# EnviromentalElements.net
KiCad netlist of a schematic drawn in Altium Designer
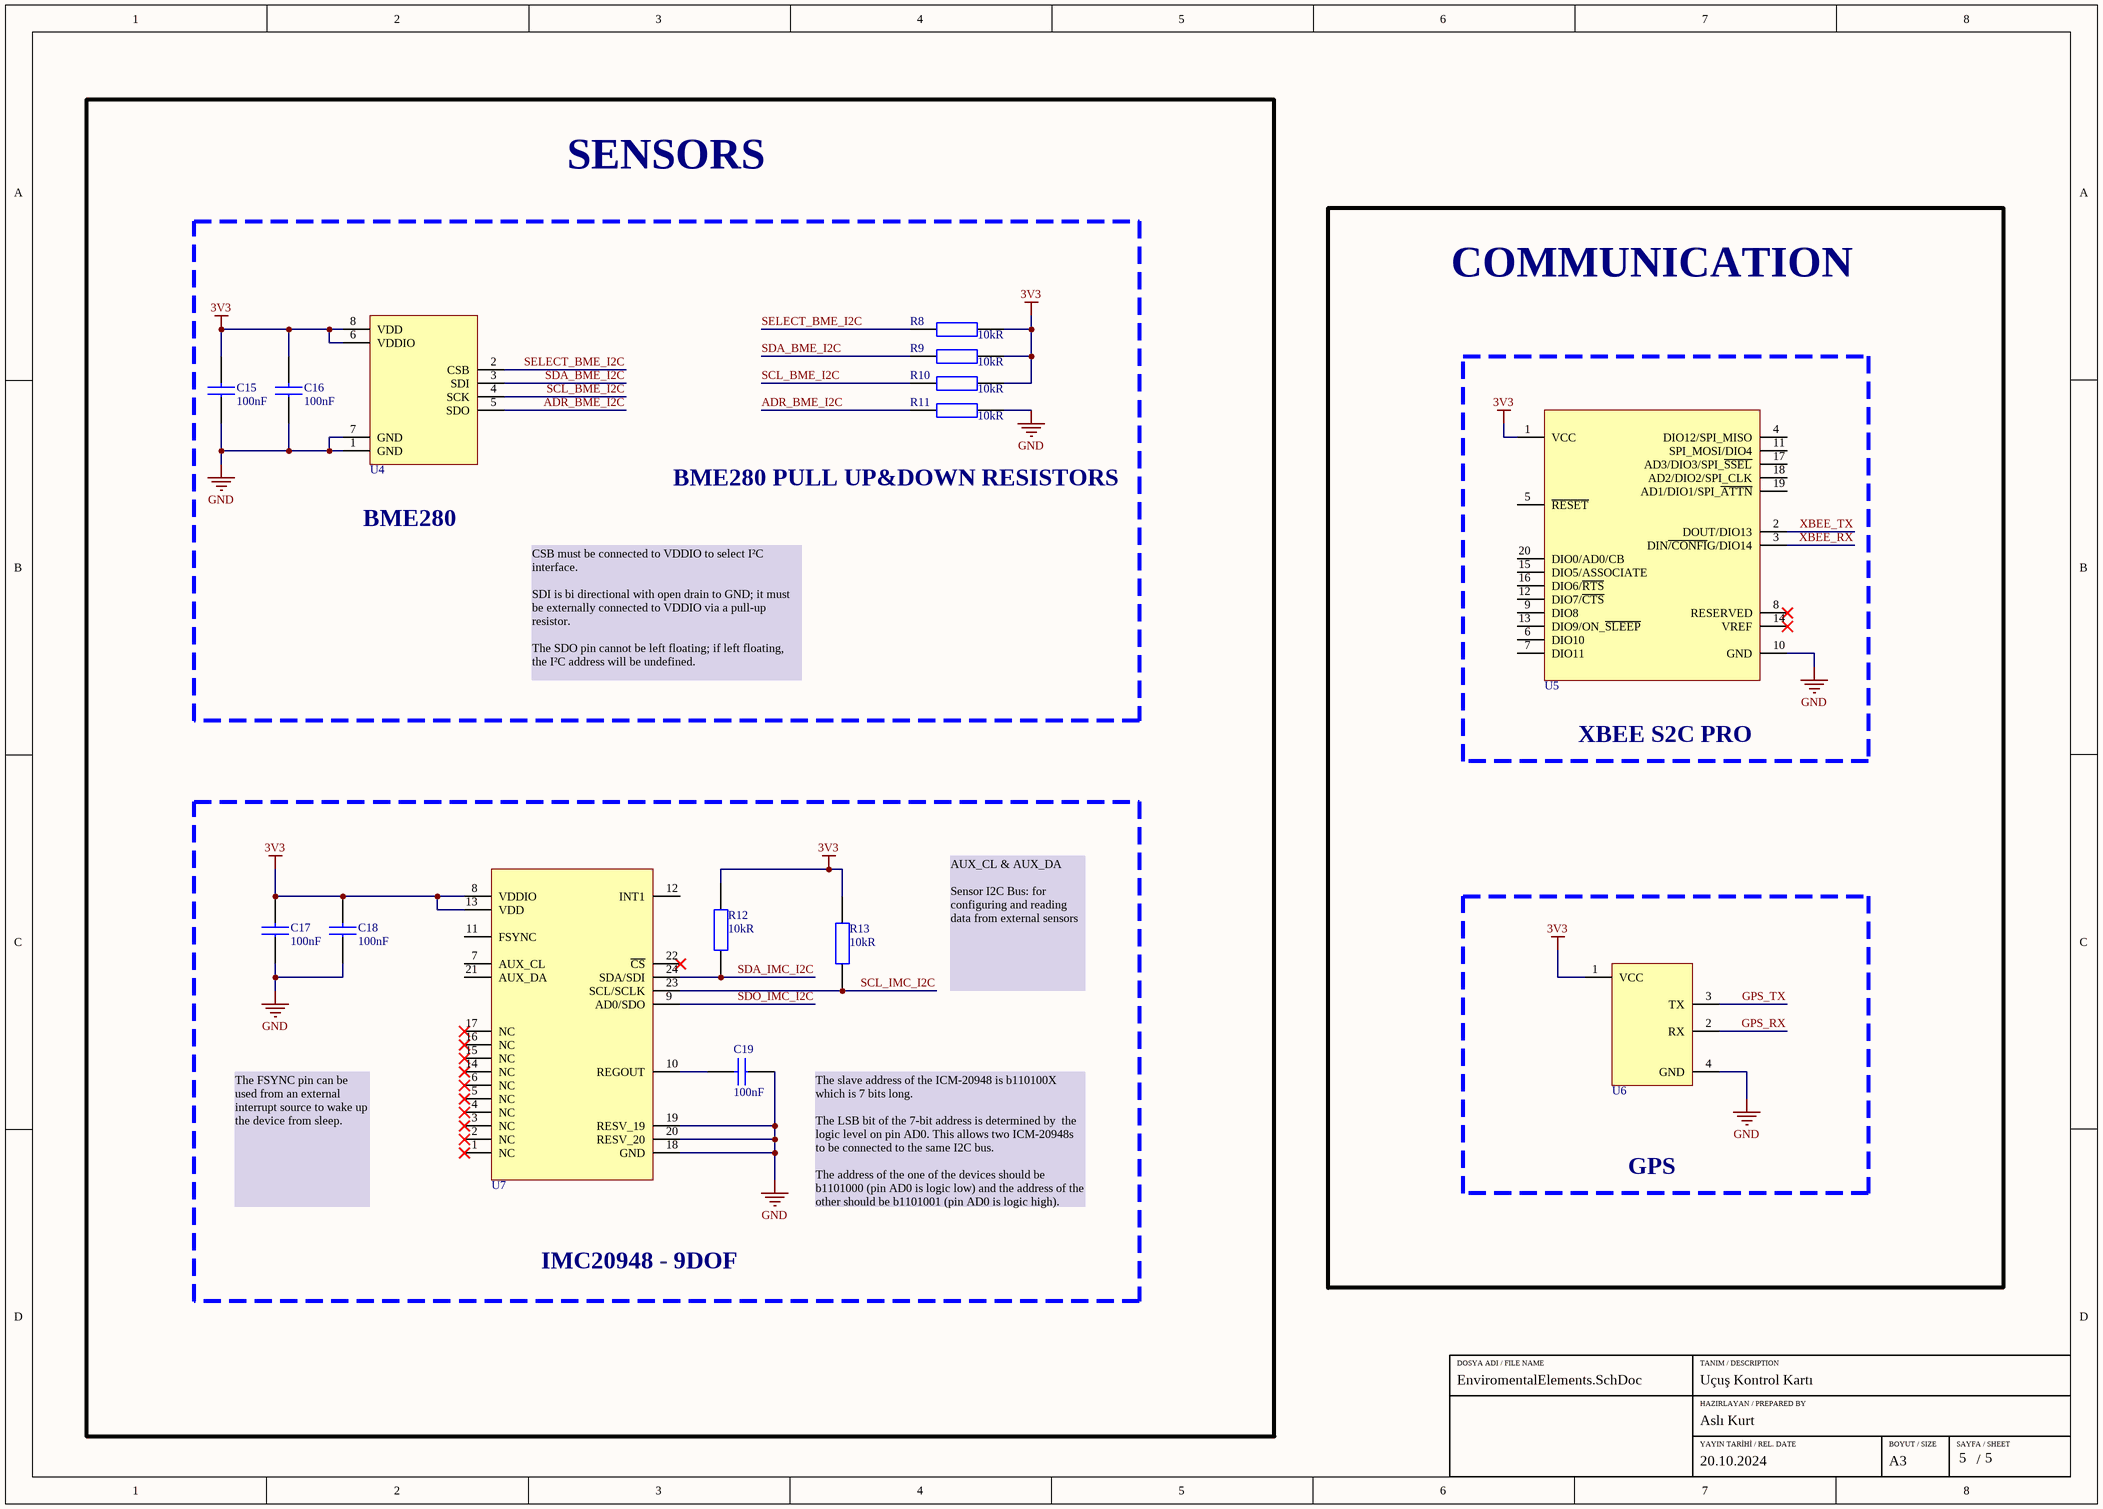
[diagram p0: EnviromentalElements.SchDoc]

(export (version "E")
  (design (tool "Eeschema 10.0.6"))
  (components
    (comp (ref "C15")
      (value "C0603C104K5RACTU")
      (footprint "CAP_0603")
      (description "CAP CER 100nF %10 0603 SMD")
      (fields
        (field (name "MANUFACTURER") "KEMET")
        (field (name "TOLERANCE") "10%")
        (field (name "CAPACITANCE") "100nF")
        (field (name "DESIGNEDBY") "Aslı Kurt")
      )
      (libsource (lib "MyLibrary") (part "CAP CER 100nF 0603"))
    )
    (comp (ref "C16")
      (value "C0603C104K5RACTU")
      (footprint "CAP_0603")
      (description "CAP CER 100nF %10 0603 SMD")
      (fields
        (field (name "MANUFACTURER") "KEMET")
        (field (name "TOLERANCE") "10%")
        (field (name "CAPACITANCE") "100nF")
        (field (name "DESIGNEDBY") "Aslı Kurt")
      )
      (libsource (lib "MyLibrary") (part "CAP CER 100nF 0603"))
    )
    (comp (ref "C17")
      (value "C0603C104K5RACTU")
      (footprint "CAP_0603")
      (description "CAP CER 100nF %10 0603 SMD")
      (fields
        (field (name "MANUFACTURER") "KEMET")
        (field (name "TOLERANCE") "10%")
        (field (name "CAPACITANCE") "100nF")
        (field (name "DESIGNEDBY") "Aslı Kurt")
      )
      (libsource (lib "MyLibrary") (part "CAP CER 100nF 0603"))
    )
    (comp (ref "C18")
      (value "C0603C104K5RACTU")
      (footprint "CAP_0603")
      (description "CAP CER 100nF %10 0603 SMD")
      (fields
        (field (name "MANUFACTURER") "KEMET")
        (field (name "TOLERANCE") "10%")
        (field (name "CAPACITANCE") "100nF")
        (field (name "DESIGNEDBY") "Aslı Kurt")
      )
      (libsource (lib "MyLibrary") (part "CAP CER 100nF 0603"))
    )
    (comp (ref "C19")
      (value "C0603C104K5RACTU")
      (footprint "CAP_0603")
      (description "CAP CER 100nF %10 0603 SMD")
      (fields
        (field (name "MANUFACTURER") "KEMET")
        (field (name "TOLERANCE") "10%")
        (field (name "CAPACITANCE") "100nF")
        (field (name "DESIGNEDBY") "Aslı Kurt")
      )
      (libsource (lib "MyLibrary") (part "CAP CER 100nF 0603"))
    )
    (comp (ref "R8")
      (value "RC0603FR-0710KL")
      (footprint "RES_0603")
      (description "RES 10K %1 OHM 0603 SMD")
      (fields
        (field (name "MANUFACTURER") "Yageo")
        (field (name "TOLERANCE") "1%")
        (field (name "RESISTANCE") "10kR")
        (field (name "DESIGNEDBY") "Aslı Kurt")
      )
      (libsource (lib "MyLibrary") (part "RES 10K OHM 0603"))
    )
    (comp (ref "R9")
      (value "RC0603FR-0710KL")
      (footprint "RES_0603")
      (description "RES 10K %1 OHM 0603 SMD")
      (fields
        (field (name "MANUFACTURER") "Yageo")
        (field (name "TOLERANCE") "1%")
        (field (name "RESISTANCE") "10kR")
        (field (name "DESIGNEDBY") "Aslı Kurt")
      )
      (libsource (lib "MyLibrary") (part "RES 10K OHM 0603"))
    )
    (comp (ref "R10")
      (value "RC0603FR-0710KL")
      (footprint "RES_0603")
      (description "RES 10K %1 OHM 0603 SMD")
      (fields
        (field (name "MANUFACTURER") "Yageo")
        (field (name "TOLERANCE") "1%")
        (field (name "RESISTANCE") "10kR")
        (field (name "DESIGNEDBY") "Aslı Kurt")
      )
      (libsource (lib "MyLibrary") (part "RES 10K OHM 0603"))
    )
    (comp (ref "R11")
      (value "RC0603FR-0710KL")
      (footprint "RES_0603")
      (description "RES 10K %1 OHM 0603 SMD")
      (fields
        (field (name "MANUFACTURER") "Yageo")
        (field (name "TOLERANCE") "1%")
        (field (name "RESISTANCE") "10kR")
        (field (name "DESIGNEDBY") "Aslı Kurt")
      )
      (libsource (lib "MyLibrary") (part "RES 10K OHM 0603"))
    )
    (comp (ref "R12")
      (value "RC0603FR-0710KL")
      (footprint "RES_0603")
      (description "RES 10K %1 OHM 0603 SMD")
      (fields
        (field (name "MANUFACTURER") "Yageo")
        (field (name "TOLERANCE") "1%")
        (field (name "RESISTANCE") "10kR")
        (field (name "DESIGNEDBY") "Aslı Kurt")
      )
      (libsource (lib "") (part "RES 10K OHM 0603_1"))
    )
    (comp (ref "R13")
      (value "RC0603FR-0710KL")
      (footprint "RES_0603")
      (description "RES 10K %1 OHM 0603 SMD")
      (fields
        (field (name "MANUFACTURER") "Yageo")
        (field (name "TOLERANCE") "1%")
        (field (name "RESISTANCE") "10kR")
        (field (name "DESIGNEDBY") "Aslı Kurt")
      )
      (libsource (lib "") (part "RES 10K OHM 0603_1"))
    )
    (comp (ref "U4")
      (value "BME280")
      (footprint "8-VFLGA")
      (description "Pressure, Temperature and Humidity Sensor Digital Output 1.8V 8-Pin LGA T/R")
      (fields (field (name "MANUFACTURER") "Bosch") (field (name "DESIGNEDBY") "Aslı Kurt"))
      (libsource (lib "MyLibrary") (part "BME280"))
    )
    (comp (ref "U5")
      (value "XBEE S2C PRO")
      (footprint "XBEE_S2C_PRO")
      (description "XBee S2C 802.15.4, 2.4GHz TH (RPSMA)")
      (fields
        (field (name "MANUFACTURER") "Digi International")
        (field (name "MANUFACTURER PART NUMBER") "XB24CASIT-001")
        (field (name "DESIGNEDBY") "Aslı Kurt")
      )
      (libsource (lib "MyLibrary") (part "XB24CASIT-001"))
    )
    (comp (ref "U6")
      (value "GY-NEO6MV2")
      (footprint "GY-NEO6MV2")
      (description "GY-NEO6MV2 GPS Modülü - Uçuş Kontrol Sistem GPS'i")
      (fields (field (name "DESIGNEDBY") "Aslı Kurt"))
      (libsource (lib "MyLibrary") (part "GY-NEO6MV2"))
    )
    (comp (ref "U7")
      (value "ICM-20948")
      (footprint "24-TFQFN Module Exposed Pad")
      (description "Accelerometer and Gyroscope Compass 9-Axis Digital 24-Pin QFN T/R")
      (fields (field (name "MANUFACTURER") "TDK") (field (name "DESIGNEDBY") "Aslı Kurt"))
      (libsource (lib "MyLibrary") (part "ICM-20948"))
    )
  )
  (nets
    (net (code "1") (name "/ADR_BME_I2C") (class "Default")
      (node (ref "R11") (pin "1") (pinfunction "1_1") (pintype "passive"))
      (node (ref "U4") (pin "5") (pinfunction "SDO_5") (pintype "passive"))
    )
    (net (code "2") (name "/GPS_RX") (class "Default")
      (node (ref "U6") (pin "2") (pinfunction "RX_2") (pintype "passive"))
    )
    (net (code "3") (name "/GPS_TX") (class "Default")
      (node (ref "U6") (pin "3") (pinfunction "TX_3") (pintype "passive"))
    )
    (net (code "4") (name "/SCL_BME_I2C") (class "Default")
      (node (ref "R10") (pin "1") (pinfunction "1_1") (pintype "passive"))
      (node (ref "U4") (pin "4") (pinfunction "SCK_4") (pintype "passive"))
    )
    (net (code "5") (name "/SCL_IMC_I2C") (class "Default")
      (node (ref "R13") (pin "1") (pinfunction "1_1") (pintype "passive"))
      (node (ref "U7") (pin "23") (pinfunction "SCL/SCLK_23") (pintype "passive"))
    )
    (net (code "6") (name "/SDA_BME_I2C") (class "Default")
      (node (ref "R9") (pin "1") (pinfunction "1_1") (pintype "passive"))
      (node (ref "U4") (pin "3") (pinfunction "SDI_3") (pintype "passive"))
    )
    (net (code "7") (name "/SDA_IMC_I2C") (class "Default")
      (node (ref "R12") (pin "1") (pinfunction "1_1") (pintype "passive"))
      (node (ref "U7") (pin "24") (pinfunction "SDA/SDI_24") (pintype "passive"))
    )
    (net (code "8") (name "/SDO_IMC_I2C") (class "Default")
      (node (ref "U7") (pin "9") (pinfunction "AD0/SDO_9") (pintype "passive"))
    )
    (net (code "9") (name "/SELECT_BME_I2C") (class "Default")
      (node (ref "R8") (pin "1") (pinfunction "1_1") (pintype "passive"))
      (node (ref "U4") (pin "2") (pinfunction "CSB_2") (pintype "passive"))
    )
    (net (code "10") (name "/XBEE_RX") (class "Default")
      (node (ref "U5") (pin "3") (pinfunction "DIN~{/CONFI}G/DIO14_3") (pintype "passive"))
    )
    (net (code "11") (name "/XBEE_TX") (class "Default")
      (node (ref "U5") (pin "2") (pinfunction "DOUT/DIO13_2") (pintype "passive"))
    )
    (net (code "12") (name "3V3") (class "Default")
      (node (ref "C15") (pin "2") (pinfunction "2_2") (pintype "passive"))
      (node (ref "C16") (pin "2") (pinfunction "2_2") (pintype "passive"))
      (node (ref "C17") (pin "2") (pinfunction "2_2") (pintype "passive"))
      (node (ref "C18") (pin "2") (pinfunction "2_2") (pintype "passive"))
      (node (ref "R10") (pin "2") (pinfunction "2_2") (pintype "passive"))
      (node (ref "R12") (pin "2") (pinfunction "2_2") (pintype "passive"))
      (node (ref "R13") (pin "2") (pinfunction "2_2") (pintype "passive"))
      (node (ref "R8") (pin "2") (pinfunction "2_2") (pintype "passive"))
      (node (ref "R9") (pin "2") (pinfunction "2_2") (pintype "passive"))
      (node (ref "U4") (pin "6") (pinfunction "VDDIO_6") (pintype "passive"))
      (node (ref "U4") (pin "8") (pinfunction "VDD_8") (pintype "passive"))
      (node (ref "U5") (pin "1") (pinfunction "VCC_1") (pintype "passive"))
      (node (ref "U6") (pin "1") (pinfunction "VCC_1") (pintype "passive"))
      (node (ref "U7") (pin "13") (pinfunction "VDD_13") (pintype "passive"))
      (node (ref "U7") (pin "8") (pinfunction "VDDIO_8") (pintype "passive"))
    )
    (net (code "13") (name "GND") (class "Default")
      (node (ref "C15") (pin "1") (pinfunction "1_1") (pintype "passive"))
      (node (ref "C16") (pin "1") (pinfunction "1_1") (pintype "passive"))
      (node (ref "C17") (pin "1") (pinfunction "1_1") (pintype "passive"))
      (node (ref "C18") (pin "1") (pinfunction "1_1") (pintype "passive"))
      (node (ref "C19") (pin "1") (pinfunction "1_1") (pintype "passive"))
      (node (ref "R11") (pin "2") (pinfunction "2_2") (pintype "passive"))
      (node (ref "U4") (pin "1") (pinfunction "GND_1") (pintype "passive"))
      (node (ref "U4") (pin "7") (pinfunction "GND_7") (pintype "passive"))
      (node (ref "U5") (pin "10") (pinfunction "GND_10") (pintype "passive"))
      (node (ref "U6") (pin "4") (pinfunction "GND_4") (pintype "passive"))
      (node (ref "U7") (pin "18") (pinfunction "GND_18") (pintype "passive"))
      (node (ref "U7") (pin "19") (pinfunction "RESV_19_19") (pintype "passive"))
      (node (ref "U7") (pin "20") (pinfunction "RESV_20_20") (pintype "passive"))
    )
    (net (code "14") (name "Net-(U7-REGOUT)") (class "Default")
      (node (ref "C19") (pin "2") (pinfunction "2_2") (pintype "passive"))
      (node (ref "U7") (pin "10") (pinfunction "REGOUT_10") (pintype "passive"))
    )
    (net (code "15") (name "unconnected-(U5-AD1{slash}DIO1{slash}SPI_~{ATTN}-Pad19)") (class "Default")
      (node (ref "U5") (pin "19") (pinfunction "AD1/DIO1/SPI_~{ATTN}_19") (pintype "passive"))
    )
    (net (code "16") (name "unconnected-(U5-AD2{slash}DIO2{slash}SPI_CLK-Pad18)") (class "Default")
      (node (ref "U5") (pin "18") (pinfunction "AD2/DIO2/SPI_CLK_18") (pintype "passive"))
    )
    (net (code "17") (name "unconnected-(U5-AD3{slash}DIO3{slash}SPI_~{SSEL}-Pad17)") (class "Default")
      (node (ref "U5") (pin "17") (pinfunction "AD3/DIO3/SPI_~{SSEL}_17") (pintype "passive"))
    )
    (net (code "18") (name "unconnected-(U5-DIO0{slash}AD0{slash}CB-Pad20)") (class "Default")
      (node (ref "U5") (pin "20") (pinfunction "DIO0/AD0/CB_20") (pintype "passive"))
    )
    (net (code "19") (name "unconnected-(U5-DIO5{slash}ASSOCIATE-Pad15)") (class "Default")
      (node (ref "U5") (pin "15") (pinfunction "DIO5/ASSOCIATE_15") (pintype "passive"))
    )
    (net (code "20") (name "unconnected-(U5-DIO6{slash}~{RTS}-Pad16)") (class "Default")
      (node (ref "U5") (pin "16") (pinfunction "DIO6/~{RTS}_16") (pintype "passive"))
    )
    (net (code "21") (name "unconnected-(U5-DIO7{slash}~{CTS}-Pad12)") (class "Default")
      (node (ref "U5") (pin "12") (pinfunction "DIO7/~{CTS}_12") (pintype "passive"))
    )
    (net (code "22") (name "unconnected-(U5-DIO8-Pad9)") (class "Default")
      (node (ref "U5") (pin "9") (pinfunction "DIO8_9") (pintype "passive"))
    )
    (net (code "23") (name "unconnected-(U5-DIO9{slash}ON_~{SLEEP}-Pad13)") (class "Default")
      (node (ref "U5") (pin "13") (pinfunction "DIO9/ON_~{SLEEP}_13") (pintype "passive"))
    )
    (net (code "24") (name "unconnected-(U5-DIO10-Pad6)") (class "Default")
      (node (ref "U5") (pin "6") (pinfunction "DIO10_6") (pintype "passive"))
    )
    (net (code "25") (name "unconnected-(U5-DIO11-Pad7)") (class "Default")
      (node (ref "U5") (pin "7") (pinfunction "DIO11_7") (pintype "passive"))
    )
    (net (code "26") (name "unconnected-(U5-DIO12{slash}SPI_MISO-Pad4)") (class "Default")
      (node (ref "U5") (pin "4") (pinfunction "DIO12/SPI_MISO_4") (pintype "passive"))
    )
    (net (code "27") (name "unconnected-(U5-RESERVED-Pad8)") (class "Default")
      (node (ref "U5") (pin "8") (pinfunction "RESERVED_8") (pintype "passive+no_connect"))
    )
    (net (code "28") (name "unconnected-(U5-SPI_MOSI{slash}DIO4-Pad11)") (class "Default")
      (node (ref "U5") (pin "11") (pinfunction "SPI_MOSI/DIO4_11") (pintype "passive"))
    )
    (net (code "29") (name "unconnected-(U5-VREF-Pad14)") (class "Default")
      (node (ref "U5") (pin "14") (pinfunction "VREF_14") (pintype "passive+no_connect"))
    )
    (net (code "30") (name "unconnected-(U5-~{RESET}-Pad5)") (class "Default")
      (node (ref "U5") (pin "5") (pinfunction "~{RESET}_5") (pintype "passive"))
    )
    (net (code "31") (name "unconnected-(U7-AUX_CL-Pad7)") (class "Default")
      (node (ref "U7") (pin "7") (pinfunction "AUX_CL_7") (pintype "passive"))
    )
    (net (code "32") (name "unconnected-(U7-AUX_DA-Pad21)") (class "Default")
      (node (ref "U7") (pin "21") (pinfunction "AUX_DA_21") (pintype "passive"))
    )
    (net (code "33") (name "unconnected-(U7-FSYNC-Pad11)") (class "Default")
      (node (ref "U7") (pin "11") (pinfunction "FSYNC_11") (pintype "passive"))
    )
    (net (code "34") (name "unconnected-(U7-INT1-Pad12)") (class "Default")
      (node (ref "U7") (pin "12") (pinfunction "INT1_12") (pintype "passive"))
    )
    (net (code "35") (name "unconnected-(U7-NC-Pad1)") (class "Default")
      (node (ref "U7") (pin "1") (pinfunction "NC_1") (pintype "passive+no_connect"))
    )
    (net (code "36") (name "unconnected-(U7-NC-Pad2)") (class "Default")
      (node (ref "U7") (pin "2") (pinfunction "NC_2") (pintype "passive+no_connect"))
    )
    (net (code "37") (name "unconnected-(U7-NC-Pad3)") (class "Default")
      (node (ref "U7") (pin "3") (pinfunction "NC_3") (pintype "passive+no_connect"))
    )
    (net (code "38") (name "unconnected-(U7-NC-Pad4)") (class "Default")
      (node (ref "U7") (pin "4") (pinfunction "NC_4") (pintype "passive+no_connect"))
    )
    (net (code "39") (name "unconnected-(U7-NC-Pad5)") (class "Default")
      (node (ref "U7") (pin "5") (pinfunction "NC_5") (pintype "passive+no_connect"))
    )
    (net (code "40") (name "unconnected-(U7-NC-Pad6)") (class "Default")
      (node (ref "U7") (pin "6") (pinfunction "NC_6") (pintype "passive+no_connect"))
    )
    (net (code "41") (name "unconnected-(U7-NC-Pad14)") (class "Default")
      (node (ref "U7") (pin "14") (pinfunction "NC_14") (pintype "passive+no_connect"))
    )
    (net (code "42") (name "unconnected-(U7-NC-Pad15)") (class "Default")
      (node (ref "U7") (pin "15") (pinfunction "NC_15") (pintype "passive+no_connect"))
    )
    (net (code "43") (name "unconnected-(U7-NC-Pad16)") (class "Default")
      (node (ref "U7") (pin "16") (pinfunction "NC_16") (pintype "passive+no_connect"))
    )
    (net (code "44") (name "unconnected-(U7-NC-Pad17)") (class "Default")
      (node (ref "U7") (pin "17") (pinfunction "NC_17") (pintype "passive+no_connect"))
    )
    (net (code "45") (name "unconnected-(U7-~{CS}-Pad22)") (class "Default")
      (node (ref "U7") (pin "22") (pinfunction "~{CS}_22") (pintype "passive+no_connect"))
    )
  )
)
